# openSX70-dongle_SEEED_v51.net
KiCad netlist of a schematic drawn in EAGLE
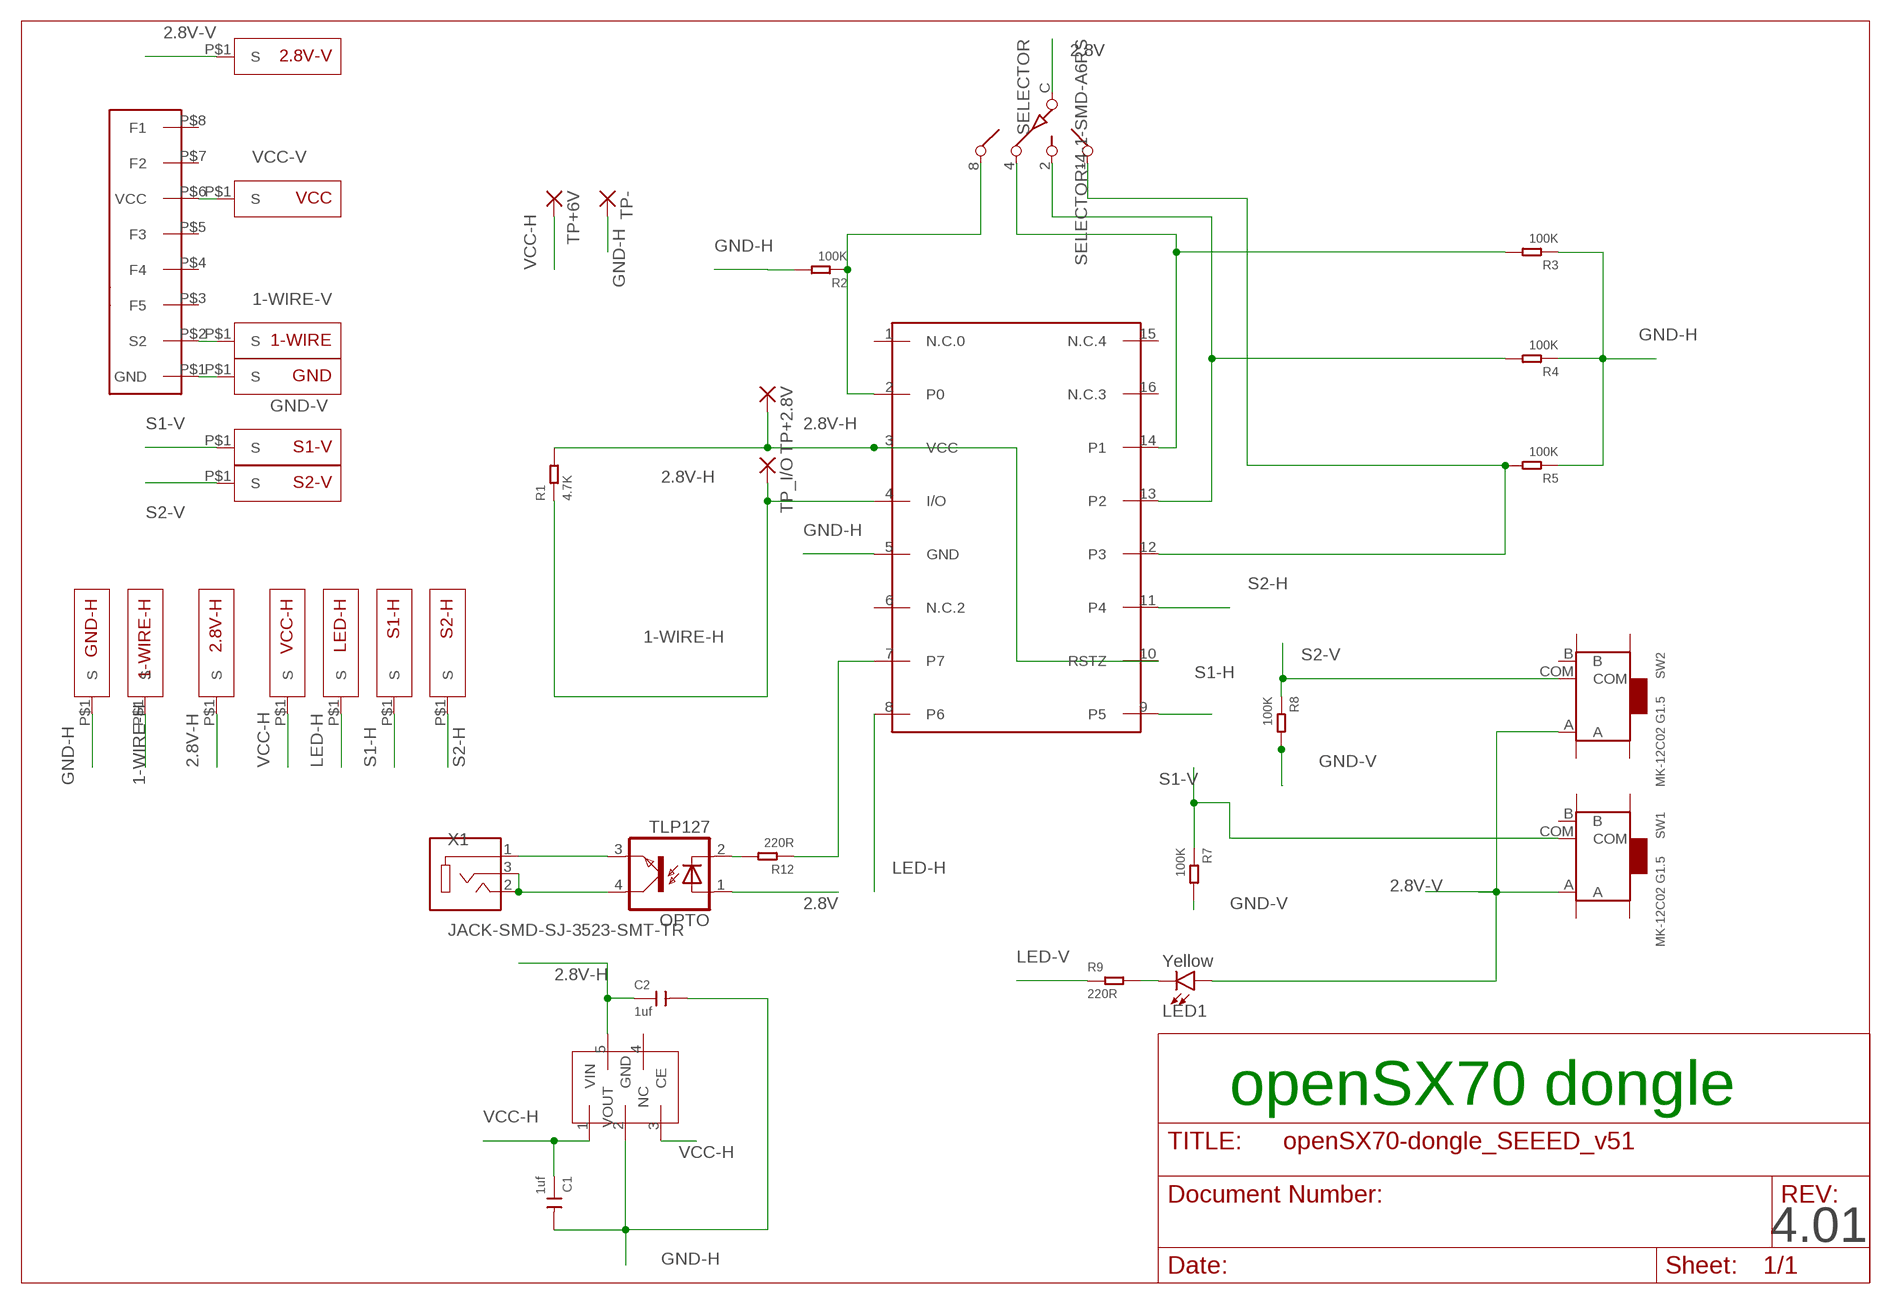
[diagram p0: schematic, sheet 1]

(export (version "E")
  (design (tool "Eeschema 10.0.6"))
  (components
    (comp (ref "1-WIRE")
      (value "SX70-S-PAD-NEW")
      (footprint "eagle-import:SX70-S-PAD2")
      (libsource (lib "eagle-import") (part "SX70-S-PAD-NEW"))
    )
    (comp (ref "1-WIRE-H")
      (value "SX70-S-PAD-NEW")
      (footprint "eagle-import:SX70-S-PAD2")
      (libsource (lib "eagle-import") (part "SX70-S-PAD-NEW"))
    )
    (comp (ref "2.8V-H")
      (value "SX70-S-PAD-NEW")
      (footprint "eagle-import:SX70-S-PAD2")
      (libsource (lib "eagle-import") (part "SX70-S-PAD-NEW"))
    )
    (comp (ref "2.8V-V")
      (value "SX70-S-PAD-NEW")
      (footprint "eagle-import:SX70-S-PAD2")
      (libsource (lib "eagle-import") (part "SX70-S-PAD-NEW"))
    )
    (comp (ref "C1")
      (value "1uf")
      (footprint "eagle-import:C0603")
      (fields (field (name "MPN") "CC0603KRX7R8BB105"))
      (libsource (lib "eagle-import") (part "CERAMIC-1UF-25V-10%-X7R(0603)"))
    )
    (comp (ref "C2")
      (value "1uf")
      (footprint "eagle-import:C0603")
      (fields (field (name "MPN") "CC0603KRX7R8BB105"))
      (libsource (lib "eagle-import") (part "CERAMIC-1UF-25V-10%-X7R(0603)"))
    )
    (comp (ref "DS2408")
      (value "DS2408")
      (footprint "eagle-import:SO16")
      (libsource (lib "eagle-import") (part "DS2408"))
    )
    (comp (ref "GND")
      (value "SX70-S-PAD-NEW")
      (footprint "eagle-import:SX70-S-PAD2")
      (libsource (lib "eagle-import") (part "SX70-S-PAD-NEW"))
    )
    (comp (ref "GND-H")
      (value "SX70-S-PAD-NEW")
      (footprint "eagle-import:SX70-S-PAD2")
      (libsource (lib "eagle-import") (part "SX70-S-PAD-NEW"))
    )
    (comp (ref "LED-H")
      (value "SX70-S-PAD-NEW")
      (footprint "eagle-import:SX70-S-PAD2")
      (libsource (lib "eagle-import") (part "SX70-S-PAD-NEW"))
    )
    (comp (ref "LED1")
      (value "Yellow")
      (footprint "eagle-import:LED-1206")
      (libsource (lib "eagle-import") (part "LED-YELLOWLILYPAD"))
    )
    (comp (ref "OPTO")
      (value "TLP127")
      (footprint "eagle-import:SO-4")
      (libsource (lib "eagle-import") (part "TLP127"))
    )
    (comp (ref "R1")
      (value "4.7K")
      (footprint "eagle-import:R0603")
      (fields (field (name "MPN") "RC0603JR-074K7L"))
      (libsource (lib "eagle-import") (part "SMD-RES-4.7K-5%-1/10W(0603)"))
    )
    (comp (ref "R2")
      (value "100K")
      (footprint "eagle-import:R0603")
      (fields (field (name "MPN") "RC0603FR-07100KL"))
      (libsource (lib "eagle-import") (part "SMD-RES-100K-1%-1/10W(0603)"))
    )
    (comp (ref "R3")
      (value "100K")
      (footprint "eagle-import:R0603")
      (fields (field (name "MPN") "RC0603FR-07100KL"))
      (libsource (lib "eagle-import") (part "SMD-RES-100K-1%-1/10W(0603)"))
    )
    (comp (ref "R4")
      (value "100K")
      (footprint "eagle-import:R0603")
      (fields (field (name "MPN") "RC0603FR-07100KL"))
      (libsource (lib "eagle-import") (part "SMD-RES-100K-1%-1/10W(0603)"))
    )
    (comp (ref "R5")
      (value "100K")
      (footprint "eagle-import:R0603")
      (fields (field (name "MPN") "RC0603FR-07100KL"))
      (libsource (lib "eagle-import") (part "SMD-RES-100K-1%-1/10W(0603)"))
    )
    (comp (ref "R7")
      (value "100K")
      (footprint "eagle-import:R0603")
      (fields (field (name "MPN") "RC0603FR-07100KL"))
      (libsource (lib "eagle-import") (part "SMD-RES-100K-1%-1/10W(0603)"))
    )
    (comp (ref "R8")
      (value "100K")
      (footprint "eagle-import:R0603")
      (fields (field (name "MPN") "RC0603FR-07100KL"))
      (libsource (lib "eagle-import") (part "SMD-RES-100K-1%-1/10W(0603)"))
    )
    (comp (ref "R9")
      (value "220R")
      (footprint "eagle-import:R0603")
      (fields (field (name "MPN") "RC0603JR-07220RL"))
      (libsource (lib "eagle-import") (part "SMD-RES-220R-5%-1/10W(0603)"))
    )
    (comp (ref "R12")
      (value "220R")
      (footprint "eagle-import:R0603")
      (fields (field (name "MPN") "RC0603JR-07220RL"))
      (libsource (lib "eagle-import") (part "SMD-RES-220R-5%-1/10W(0603)"))
    )
    (comp (ref "REG")
      (value "NCP4688")
      (footprint "eagle-import:SOT-23-5")
      (libsource (lib "eagle-import") (part "NCP4688"))
    )
    (comp (ref "S1-H")
      (value "SX70-S-PAD-NEW")
      (footprint "eagle-import:SX70-S-PAD2")
      (libsource (lib "eagle-import") (part "SX70-S-PAD-NEW"))
    )
    (comp (ref "S1-V")
      (value "SX70-S-PAD-NEW")
      (footprint "eagle-import:SX70-S-PAD2")
      (libsource (lib "eagle-import") (part "SX70-S-PAD-NEW"))
    )
    (comp (ref "S2-H")
      (value "SX70-S-PAD-NEW")
      (footprint "eagle-import:SX70-S-PAD2")
      (libsource (lib "eagle-import") (part "SX70-S-PAD-NEW"))
    )
    (comp (ref "S2-V")
      (value "SX70-S-PAD-NEW")
      (footprint "eagle-import:SX70-S-PAD2")
      (libsource (lib "eagle-import") (part "SX70-S-PAD-NEW"))
    )
    (comp (ref "SELECTOR")
      (value "SELECTOR-4-1-SMD-A6RS")
      (footprint "eagle-import:A6RS-161RS")
      (libsource (lib "eagle-import") (part "SELECTOR-4-1-SMD-A6RS"))
    )
    (comp (ref "SW1")
      (value "MK-12C02 G1.5")
      (footprint "eagle-import:SW7-SMD-L6.7X2.7X3.2MM")
      (libsource (lib "eagle-import") (part "SMD-TOGGLE-SWITCH-ON-ON(3+4P-6.7X2.7MM)"))
    )
    (comp (ref "SW2")
      (value "MK-12C02 G1.5")
      (footprint "eagle-import:SW7-SMD-L6.7X2.7X3.2MM")
      (libsource (lib "eagle-import") (part "SMD-TOGGLE-SWITCH-ON-ON(3+4P-6.7X2.7MM)"))
    )
    (comp (ref "TP+2.8V")
      (value "SMD2")
      (footprint "eagle-import:SMD1,27-2,54")
      (libsource (lib "eagle-import") (part "SMD2"))
    )
    (comp (ref "TP+6V")
      (value "SMD2")
      (footprint "eagle-import:SMD1,27-2,54")
      (libsource (lib "eagle-import") (part "SMD2"))
    )
    (comp (ref "TP-")
      (value "SMD2")
      (footprint "eagle-import:SMD1,27-2,54")
      (libsource (lib "eagle-import") (part "SMD2"))
    )
    (comp (ref "TP_I/O")
      (value "SMD2")
      (footprint "eagle-import:SMD1,27-2,54")
      (libsource (lib "eagle-import") (part "SMD2"))
    )
    (comp (ref "U$1")
      (value "FLASH-EDGE-CONNECTOR")
      (footprint "eagle-import:FLASH-EDGE-8")
      (libsource (lib "eagle-import") (part "FLASH-EDGE-CONNECTOR"))
    )
    (comp (ref "VCC")
      (value "SX70-S-PAD-NEW")
      (footprint "eagle-import:SX70-S-PAD2")
      (libsource (lib "eagle-import") (part "SX70-S-PAD-NEW"))
    )
    (comp (ref "VCC-H")
      (value "SX70-S-PAD-NEW")
      (footprint "eagle-import:SX70-S-PAD2")
      (libsource (lib "eagle-import") (part "SX70-S-PAD-NEW"))
    )
    (comp (ref "X1")
      (value "JACK-SMD-SJ-3523-SMT-TR")
      (footprint "eagle-import:CUI_SJ-3523-SMT-TR")
      (fields (field (name "MF") "CUI Inc.") (field (name "MP") "SJ-3523-SMT-TR"))
      (libsource (lib "eagle-import") (part "JACK-SMD-SJ-3523-SMT-TR"))
    )
  )
  (nets
    (net (code "1") (name "/1-WIRE-H") (class "Default")
      (node (ref "1-WIRE-H") (pin "P$1") (pinfunction "S_P$1") (pintype "bidirectional"))
      (node (ref "DS2408") (pin "4") (pinfunction "I/O_4") (pintype "bidirectional"))
      (node (ref "R1") (pin "1") (pinfunction "1_1") (pintype "passive"))
      (node (ref "TP_I/O") (pin "1") (pinfunction "P_1") (pintype "passive"))
    )
    (net (code "2") (name "/1-WIRE-V") (class "Default")
      (node (ref "1-WIRE") (pin "P$1") (pinfunction "S_P$1") (pintype "bidirectional"))
      (node (ref "U$1") (pin "P$2") (pinfunction "S2_P$2") (pintype "bidirectional"))
    )
    (net (code "3") (name "/2.8V") (class "Default")
      (node (ref "OPTO") (pin "1") (pinfunction "A_1") (pintype "passive"))
      (node (ref "SELECTOR") (pin "C") (pinfunction "C_C") (pintype "passive"))
    )
    (net (code "4") (name "/2.8V-H") (class "Default")
      (node (ref "2.8V-H") (pin "P$1") (pinfunction "S_P$1") (pintype "bidirectional"))
      (node (ref "C2") (pin "1") (pinfunction "1_1") (pintype "passive"))
      (node (ref "DS2408") (pin "10") (pinfunction "RSTZ_10") (pintype "bidirectional"))
      (node (ref "DS2408") (pin "3") (pinfunction "VCC_3") (pintype "bidirectional"))
      (node (ref "R1") (pin "2") (pinfunction "2_2") (pintype "passive"))
      (node (ref "REG") (pin "5") (pinfunction "VOUT_5") (pintype "bidirectional"))
      (node (ref "TP+2.8V") (pin "1") (pinfunction "P_1") (pintype "passive"))
    )
    (net (code "5") (name "/2.8V-V") (class "Default")
      (node (ref "2.8V-V") (pin "P$1") (pinfunction "S_P$1") (pintype "bidirectional"))
      (node (ref "LED1") (pin "A") (pinfunction "A_A") (pintype "passive"))
      (node (ref "SW1") (pin "A") (pinfunction "A_A") (pintype "bidirectional"))
      (node (ref "SW2") (pin "A") (pinfunction "A_A") (pintype "bidirectional"))
    )
    (net (code "6") (name "/GND-H") (class "Default")
      (node (ref "C1") (pin "2") (pinfunction "2_2") (pintype "passive"))
      (node (ref "C2") (pin "2") (pinfunction "2_2") (pintype "passive"))
      (node (ref "DS2408") (pin "5") (pinfunction "GND_5") (pintype "bidirectional"))
      (node (ref "GND-H") (pin "P$1") (pinfunction "S_P$1") (pintype "bidirectional"))
      (node (ref "R2") (pin "2") (pinfunction "2_2") (pintype "passive"))
      (node (ref "R3") (pin "1") (pinfunction "1_1") (pintype "passive"))
      (node (ref "R4") (pin "1") (pinfunction "1_1") (pintype "passive"))
      (node (ref "R5") (pin "1") (pinfunction "1_1") (pintype "passive"))
      (node (ref "REG") (pin "2") (pinfunction "GND_2") (pintype "bidirectional"))
      (node (ref "TP-") (pin "1") (pinfunction "P_1") (pintype "passive"))
    )
    (net (code "7") (name "/GND-V") (class "Default")
      (node (ref "GND") (pin "P$1") (pinfunction "S_P$1") (pintype "bidirectional"))
      (node (ref "R7") (pin "2") (pinfunction "2_2") (pintype "passive"))
      (node (ref "R8") (pin "2") (pinfunction "2_2") (pintype "passive"))
      (node (ref "U$1") (pin "P$1") (pinfunction "GND_P$1") (pintype "bidirectional"))
    )
    (net (code "8") (name "/LED-H") (class "Default")
      (node (ref "DS2408") (pin "8") (pinfunction "P6_8") (pintype "bidirectional"))
      (node (ref "LED-H") (pin "P$1") (pinfunction "S_P$1") (pintype "bidirectional"))
    )
    (net (code "9") (name "/LED-V") (class "Default")
      (node (ref "R9") (pin "1") (pinfunction "1_1") (pintype "passive"))
    )
    (net (code "10") (name "/S1-H") (class "Default")
      (node (ref "DS2408") (pin "9") (pinfunction "P5_9") (pintype "bidirectional"))
      (node (ref "S1-H") (pin "P$1") (pinfunction "S_P$1") (pintype "bidirectional"))
    )
    (net (code "11") (name "/S1-V") (class "Default")
      (node (ref "R7") (pin "1") (pinfunction "1_1") (pintype "passive"))
      (node (ref "S1-V") (pin "P$1") (pinfunction "S_P$1") (pintype "bidirectional"))
      (node (ref "SW1") (pin "COM") (pinfunction "COM_COM") (pintype "bidirectional"))
    )
    (net (code "12") (name "/S2-H") (class "Default")
      (node (ref "DS2408") (pin "11") (pinfunction "P4_11") (pintype "bidirectional"))
      (node (ref "S2-H") (pin "P$1") (pinfunction "S_P$1") (pintype "bidirectional"))
    )
    (net (code "13") (name "/S2-V") (class "Default")
      (node (ref "R8") (pin "1") (pinfunction "1_1") (pintype "passive"))
      (node (ref "S2-V") (pin "P$1") (pinfunction "S_P$1") (pintype "bidirectional"))
      (node (ref "SW2") (pin "COM") (pinfunction "COM_COM") (pintype "bidirectional"))
    )
    (net (code "14") (name "/VCC-H") (class "Default")
      (node (ref "C1") (pin "1") (pinfunction "1_1") (pintype "passive"))
      (node (ref "REG") (pin "1") (pinfunction "VIN_1") (pintype "bidirectional"))
      (node (ref "REG") (pin "3") (pinfunction "CE_3") (pintype "bidirectional"))
      (node (ref "TP+6V") (pin "1") (pinfunction "P_1") (pintype "passive"))
      (node (ref "VCC-H") (pin "P$1") (pinfunction "S_P$1") (pintype "bidirectional"))
    )
    (net (code "15") (name "/VCC-V") (class "Default")
      (node (ref "U$1") (pin "P$6") (pinfunction "VCC_P$6") (pintype "bidirectional"))
      (node (ref "VCC") (pin "P$1") (pinfunction "S_P$1") (pintype "bidirectional"))
    )
    (net (code "16") (name "Net-(DS2408-P0)") (class "Default")
      (node (ref "DS2408") (pin "2") (pinfunction "P0_2") (pintype "bidirectional"))
      (node (ref "R2") (pin "1") (pinfunction "1_1") (pintype "passive"))
      (node (ref "SELECTOR") (pin "8") (pinfunction "8_8") (pintype "passive"))
    )
    (net (code "17") (name "Net-(DS2408-P1)") (class "Default")
      (node (ref "DS2408") (pin "14") (pinfunction "P1_14") (pintype "bidirectional"))
      (node (ref "R3") (pin "2") (pinfunction "2_2") (pintype "passive"))
      (node (ref "SELECTOR") (pin "4") (pinfunction "4_4") (pintype "passive"))
    )
    (net (code "18") (name "Net-(DS2408-P2)") (class "Default")
      (node (ref "DS2408") (pin "13") (pinfunction "P2_13") (pintype "bidirectional"))
      (node (ref "R4") (pin "2") (pinfunction "2_2") (pintype "passive"))
      (node (ref "SELECTOR") (pin "2") (pinfunction "2_2") (pintype "passive"))
    )
    (net (code "19") (name "Net-(DS2408-P3)") (class "Default")
      (node (ref "DS2408") (pin "12") (pinfunction "P3_12") (pintype "bidirectional"))
      (node (ref "R5") (pin "2") (pinfunction "2_2") (pintype "passive"))
      (node (ref "SELECTOR") (pin "1") (pinfunction "1_1") (pintype "passive"))
    )
    (net (code "20") (name "Net-(DS2408-P7)") (class "Default")
      (node (ref "DS2408") (pin "7") (pinfunction "P7_7") (pintype "bidirectional"))
      (node (ref "R12") (pin "1") (pinfunction "1_1") (pintype "passive"))
    )
    (net (code "21") (name "Net-(LED1-PadC)") (class "Default")
      (node (ref "LED1") (pin "C") (pinfunction "C_C") (pintype "passive"))
      (node (ref "R9") (pin "2") (pinfunction "2_2") (pintype "passive"))
    )
    (net (code "22") (name "Net-(OPTO-C)") (class "Default")
      (node (ref "OPTO") (pin "2") (pinfunction "C_2") (pintype "passive"))
      (node (ref "R12") (pin "2") (pinfunction "2_2") (pintype "passive"))
    )
    (net (code "23") (name "Net-(OPTO-COL)") (class "Default")
      (node (ref "OPTO") (pin "4") (pinfunction "COL_4") (pintype "passive"))
      (node (ref "X1") (pin "2") (pinfunction "2_2") (pintype "passive"))
      (node (ref "X1") (pin "3") (pinfunction "3_3") (pintype "passive"))
    )
    (net (code "24") (name "Net-(OPTO-EMIT)") (class "Default")
      (node (ref "OPTO") (pin "3") (pinfunction "EMIT_3") (pintype "passive"))
      (node (ref "X1") (pin "1") (pinfunction "1_1") (pintype "passive"))
    )
    (net (code "25") (name "unconnected-(DS2408-N.C.0-Pad1)") (class "Default")
      (node (ref "DS2408") (pin "1") (pinfunction "N.C.0_1") (pintype "bidirectional"))
    )
    (net (code "26") (name "unconnected-(DS2408-N.C.2-Pad6)") (class "Default")
      (node (ref "DS2408") (pin "6") (pinfunction "N.C.2_6") (pintype "bidirectional"))
    )
    (net (code "27") (name "unconnected-(DS2408-N.C.3-Pad16)") (class "Default")
      (node (ref "DS2408") (pin "16") (pinfunction "N.C.3_16") (pintype "bidirectional"))
    )
    (net (code "28") (name "unconnected-(DS2408-N.C.4-Pad15)") (class "Default")
      (node (ref "DS2408") (pin "15") (pinfunction "N.C.4_15") (pintype "bidirectional"))
    )
    (net (code "29") (name "unconnected-(REG-NC-Pad4)") (class "Default")
      (node (ref "REG") (pin "4") (pinfunction "NC_4") (pintype "bidirectional"))
    )
    (net (code "30") (name "unconnected-(SW1-PadB)") (class "Default")
      (node (ref "SW1") (pin "B") (pinfunction "B_B") (pintype "bidirectional"))
    )
    (net (code "31") (name "unconnected-(SW1-PadSS1)") (class "Default")
      (node (ref "SW1") (pin "SS1") (pinfunction "SS1_SS1") (pintype "bidirectional"))
    )
    (net (code "32") (name "unconnected-(SW1-PadSS2)") (class "Default")
      (node (ref "SW1") (pin "SS2") (pinfunction "SS2_SS2") (pintype "bidirectional"))
    )
    (net (code "33") (name "unconnected-(SW1-PadSS3)") (class "Default")
      (node (ref "SW1") (pin "SS3") (pinfunction "SS3_SS3") (pintype "bidirectional"))
    )
    (net (code "34") (name "unconnected-(SW1-PadSS4)") (class "Default")
      (node (ref "SW1") (pin "SS4") (pinfunction "SS4_SS4") (pintype "bidirectional"))
    )
    (net (code "35") (name "unconnected-(SW2-PadB)") (class "Default")
      (node (ref "SW2") (pin "B") (pinfunction "B_B") (pintype "bidirectional"))
    )
    (net (code "36") (name "unconnected-(SW2-PadSS1)") (class "Default")
      (node (ref "SW2") (pin "SS1") (pinfunction "SS1_SS1") (pintype "bidirectional"))
    )
    (net (code "37") (name "unconnected-(SW2-PadSS2)") (class "Default")
      (node (ref "SW2") (pin "SS2") (pinfunction "SS2_SS2") (pintype "bidirectional"))
    )
    (net (code "38") (name "unconnected-(SW2-PadSS3)") (class "Default")
      (node (ref "SW2") (pin "SS3") (pinfunction "SS3_SS3") (pintype "bidirectional"))
    )
    (net (code "39") (name "unconnected-(SW2-PadSS4)") (class "Default")
      (node (ref "SW2") (pin "SS4") (pinfunction "SS4_SS4") (pintype "bidirectional"))
    )
    (net (code "40") (name "unconnected-(U$1-F1-PadP$8)") (class "Default")
      (node (ref "U$1") (pin "P$8") (pinfunction "F1_P$8") (pintype "bidirectional"))
    )
    (net (code "41") (name "unconnected-(U$1-F2-PadP$7)") (class "Default")
      (node (ref "U$1") (pin "P$7") (pinfunction "F2_P$7") (pintype "bidirectional"))
    )
    (net (code "42") (name "unconnected-(U$1-F3-PadP$5)") (class "Default")
      (node (ref "U$1") (pin "P$5") (pinfunction "F3_P$5") (pintype "bidirectional"))
    )
    (net (code "43") (name "unconnected-(U$1-F4-PadP$4)") (class "Default")
      (node (ref "U$1") (pin "P$4") (pinfunction "F4_P$4") (pintype "bidirectional"))
    )
    (net (code "44") (name "unconnected-(U$1-F5-PadP$3)") (class "Default")
      (node (ref "U$1") (pin "P$3") (pinfunction "F5_P$3") (pintype "bidirectional"))
    )
  )
)
